# IMU_Gesture_Recognition_Sensors.net
KiCad netlist of a schematic drawn in Altium Designer
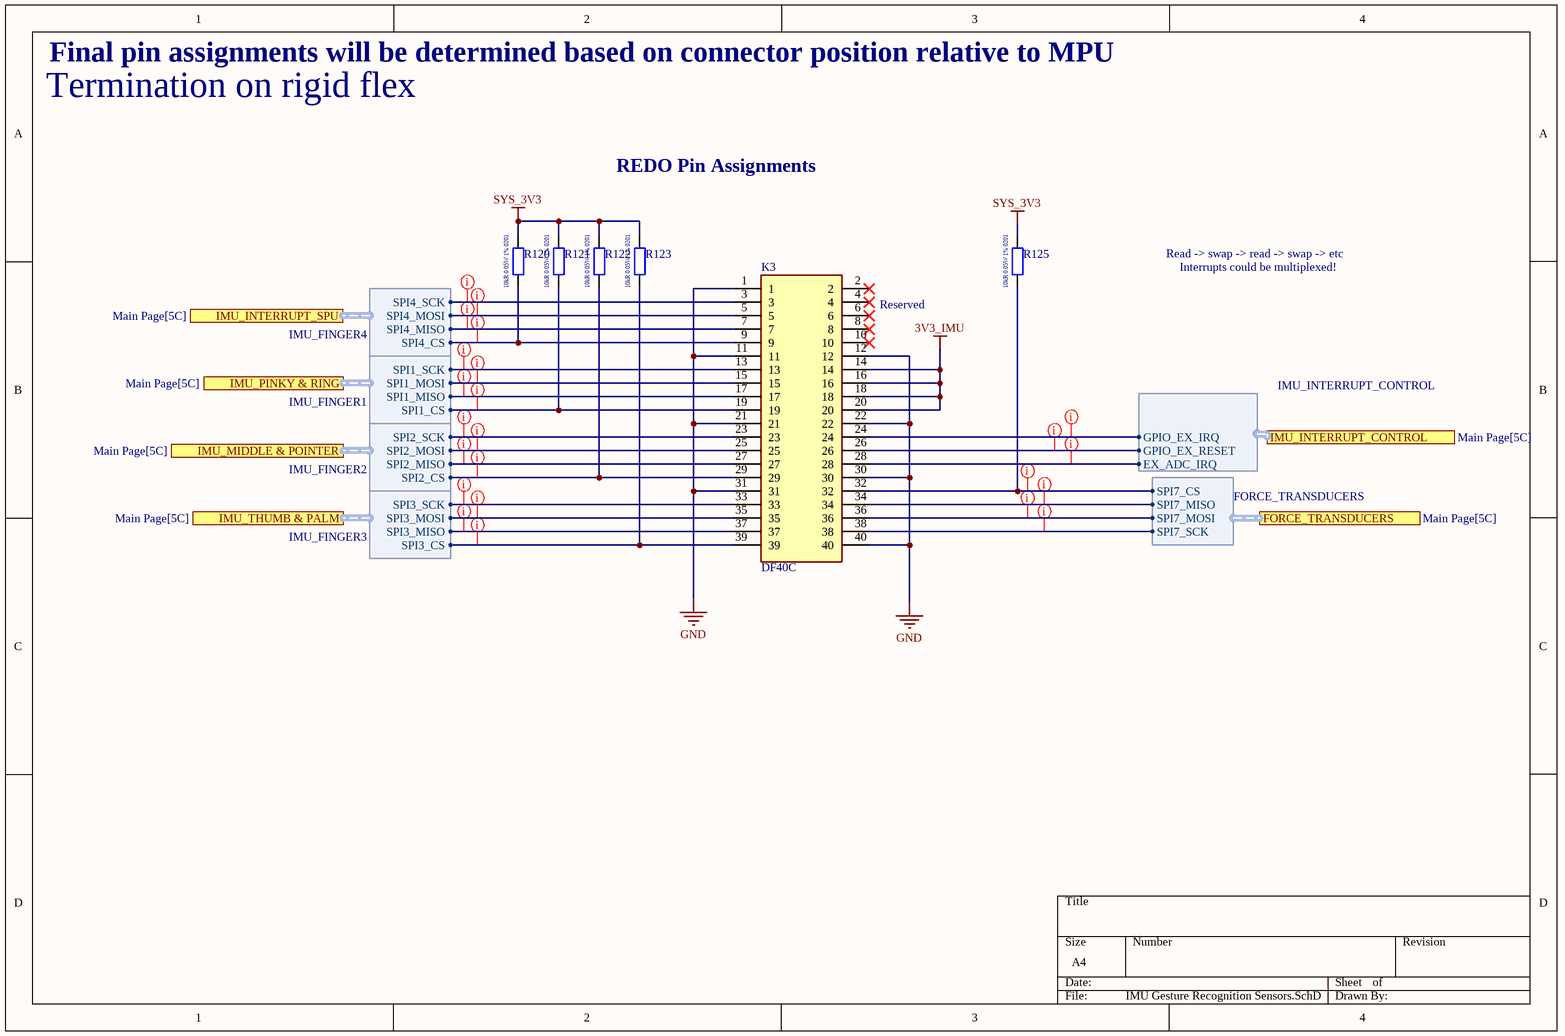
[diagram p0: IMU Gesture Recognition Sensors.SchDoc]

(export (version "E")
  (design (tool "Eeschema 10.0.6"))
  (components
    (comp (ref "K3")
      (value "DF40C")
      (footprint "HIROSE_DF40C-40DS-0.4V(51)")
      (description "40 Position Connector Receptacle, Center Strip Contacts Surface Mount Gold")
      (libsource (lib "Gesturelink Schematic Library") (part "DF40C"))
    )
    (comp (ref "R120")
      (value "ERJ-1GNF1002C")
      (footprint "RESC0603X03L")
      (description "10 kOhms ±1% 0.05W, 1/20W Chip Resistor 0201 (0603 Metric) Thick Film")
      (libsource (lib "Resistors") (part "ERJ-1GNF1002C"))
    )
    (comp (ref "R121")
      (value "ERJ-1GNF1002C")
      (footprint "RESC0603X03L")
      (description "10 kOhms ±1% 0.05W, 1/20W Chip Resistor 0201 (0603 Metric) Thick Film")
      (libsource (lib "Resistors") (part "ERJ-1GNF1002C"))
    )
    (comp (ref "R122")
      (value "ERJ-1GNF1002C")
      (footprint "RESC0603X03L")
      (description "10 kOhms ±1% 0.05W, 1/20W Chip Resistor 0201 (0603 Metric) Thick Film")
      (libsource (lib "Resistors") (part "ERJ-1GNF1002C"))
    )
    (comp (ref "R123")
      (value "ERJ-1GNF1002C")
      (footprint "RESC0603X03L")
      (description "10 kOhms ±1% 0.05W, 1/20W Chip Resistor 0201 (0603 Metric) Thick Film")
      (libsource (lib "Resistors") (part "ERJ-1GNF1002C"))
    )
    (comp (ref "R125")
      (value "ERJ-1GNF1002C")
      (footprint "RESC0603X03L")
      (description "10 kOhms ±1% 0.05W, 1/20W Chip Resistor 0201 (0603 Metric) Thick Film")
      (libsource (lib "Resistors") (part "ERJ-1GNF1002C"))
    )
  )
  (nets
    (net (code "12") (name "3V3_IMU") (class "Default")
      (node (ref "K3") (pin "14") (pinfunction "14_14") (pintype "passive"))
      (node (ref "K3") (pin "16") (pinfunction "16_16") (pintype "passive"))
      (node (ref "K3") (pin "18") (pinfunction "18_18") (pintype "passive"))
      (node (ref "K3") (pin "20") (pinfunction "20_20") (pintype "passive"))
    )
    (net (code "13") (name "GND") (class "Default")
      (node (ref "K3") (pin "1") (pinfunction "1_1") (pintype "passive"))
      (node (ref "K3") (pin "11") (pinfunction "11_11") (pintype "passive"))
      (node (ref "K3") (pin "12") (pinfunction "12_12") (pintype "passive"))
      (node (ref "K3") (pin "21") (pinfunction "21_21") (pintype "passive"))
      (node (ref "K3") (pin "22") (pinfunction "22_22") (pintype "passive"))
      (node (ref "K3") (pin "30") (pinfunction "30_30") (pintype "passive"))
      (node (ref "K3") (pin "31") (pinfunction "31_31") (pintype "passive"))
      (node (ref "K3") (pin "40") (pinfunction "40_40") (pintype "passive"))
    )
    (net (code "14") (name "Net-(K3-Pad9)") (class "Default")
      (node (ref "K3") (pin "9") (pinfunction "9_9") (pintype "passive"))
      (node (ref "R120") (pin "1") (pinfunction "1_1") (pintype "passive"))
    )
    (net (code "15") (name "Net-(K3-Pad19)") (class "Default")
      (node (ref "K3") (pin "19") (pinfunction "19_19") (pintype "passive"))
      (node (ref "R121") (pin "1") (pinfunction "1_1") (pintype "passive"))
    )
    (net (code "16") (name "Net-(K3-Pad29)") (class "Default")
      (node (ref "K3") (pin "29") (pinfunction "29_29") (pintype "passive"))
      (node (ref "R122") (pin "1") (pinfunction "1_1") (pintype "passive"))
    )
    (net (code "17") (name "Net-(K3-Pad32)") (class "Default")
      (node (ref "K3") (pin "32") (pinfunction "32_32") (pintype "passive"))
      (node (ref "R125") (pin "1") (pinfunction "1_1") (pintype "passive"))
    )
    (net (code "18") (name "Net-(K3-Pad39)") (class "Default")
      (node (ref "K3") (pin "39") (pinfunction "39_39") (pintype "passive"))
      (node (ref "R123") (pin "1") (pinfunction "1_1") (pintype "passive"))
    )
    (net (code "19") (name "SYS_3V3") (class "Default")
      (node (ref "R120") (pin "2") (pinfunction "2_2") (pintype "passive"))
      (node (ref "R121") (pin "2") (pinfunction "2_2") (pintype "passive"))
      (node (ref "R122") (pin "2") (pinfunction "2_2") (pintype "passive"))
      (node (ref "R123") (pin "2") (pinfunction "2_2") (pintype "passive"))
      (node (ref "R125") (pin "2") (pinfunction "2_2") (pintype "passive"))
    )
    (net (code "20") (name "unconnected-(K3-Pad2)") (class "Default")
      (node (ref "K3") (pin "2") (pinfunction "2_2") (pintype "passive+no_connect"))
    )
    (net (code "21") (name "unconnected-(K3-Pad3)") (class "Default")
      (node (ref "K3") (pin "3") (pinfunction "3_3") (pintype "passive"))
    )
    (net (code "22") (name "unconnected-(K3-Pad4)") (class "Default")
      (node (ref "K3") (pin "4") (pinfunction "4_4") (pintype "passive+no_connect"))
    )
    (net (code "23") (name "unconnected-(K3-Pad5)") (class "Default")
      (node (ref "K3") (pin "5") (pinfunction "5_5") (pintype "passive"))
    )
    (net (code "24") (name "unconnected-(K3-Pad6)") (class "Default")
      (node (ref "K3") (pin "6") (pinfunction "6_6") (pintype "passive+no_connect"))
    )
    (net (code "25") (name "unconnected-(K3-Pad7)") (class "Default")
      (node (ref "K3") (pin "7") (pinfunction "7_7") (pintype "passive"))
    )
    (net (code "26") (name "unconnected-(K3-Pad8)") (class "Default")
      (node (ref "K3") (pin "8") (pinfunction "8_8") (pintype "passive+no_connect"))
    )
    (net (code "27") (name "unconnected-(K3-Pad10)") (class "Default")
      (node (ref "K3") (pin "10") (pinfunction "10_10") (pintype "passive+no_connect"))
    )
    (net (code "28") (name "unconnected-(K3-Pad13)") (class "Default")
      (node (ref "K3") (pin "13") (pinfunction "13_13") (pintype "passive"))
    )
    (net (code "29") (name "unconnected-(K3-Pad15)") (class "Default")
      (node (ref "K3") (pin "15") (pinfunction "15_15") (pintype "passive"))
    )
    (net (code "30") (name "unconnected-(K3-Pad17)") (class "Default")
      (node (ref "K3") (pin "17") (pinfunction "17_17") (pintype "passive"))
    )
    (net (code "31") (name "unconnected-(K3-Pad23)") (class "Default")
      (node (ref "K3") (pin "23") (pinfunction "23_23") (pintype "passive"))
    )
    (net (code "32") (name "unconnected-(K3-Pad24)") (class "Default")
      (node (ref "K3") (pin "24") (pinfunction "24_24") (pintype "passive"))
    )
    (net (code "33") (name "unconnected-(K3-Pad25)") (class "Default")
      (node (ref "K3") (pin "25") (pinfunction "25_25") (pintype "passive"))
    )
    (net (code "34") (name "unconnected-(K3-Pad26)") (class "Default")
      (node (ref "K3") (pin "26") (pinfunction "26_26") (pintype "passive"))
    )
    (net (code "35") (name "unconnected-(K3-Pad27)") (class "Default")
      (node (ref "K3") (pin "27") (pinfunction "27_27") (pintype "passive"))
    )
    (net (code "36") (name "unconnected-(K3-Pad28)") (class "Default")
      (node (ref "K3") (pin "28") (pinfunction "28_28") (pintype "passive"))
    )
    (net (code "37") (name "unconnected-(K3-Pad33)") (class "Default")
      (node (ref "K3") (pin "33") (pinfunction "33_33") (pintype "passive"))
    )
    (net (code "38") (name "unconnected-(K3-Pad34)") (class "Default")
      (node (ref "K3") (pin "34") (pinfunction "34_34") (pintype "passive"))
    )
    (net (code "39") (name "unconnected-(K3-Pad35)") (class "Default")
      (node (ref "K3") (pin "35") (pinfunction "35_35") (pintype "passive"))
    )
    (net (code "40") (name "unconnected-(K3-Pad36)") (class "Default")
      (node (ref "K3") (pin "36") (pinfunction "36_36") (pintype "passive"))
    )
    (net (code "41") (name "unconnected-(K3-Pad37)") (class "Default")
      (node (ref "K3") (pin "37") (pinfunction "37_37") (pintype "passive"))
    )
    (net (code "42") (name "unconnected-(K3-Pad38)") (class "Default")
      (node (ref "K3") (pin "38") (pinfunction "38_38") (pintype "passive"))
    )
  )
)
